# Metro_Mini_Rev_B.net
KiCad netlist of a schematic drawn in EAGLE
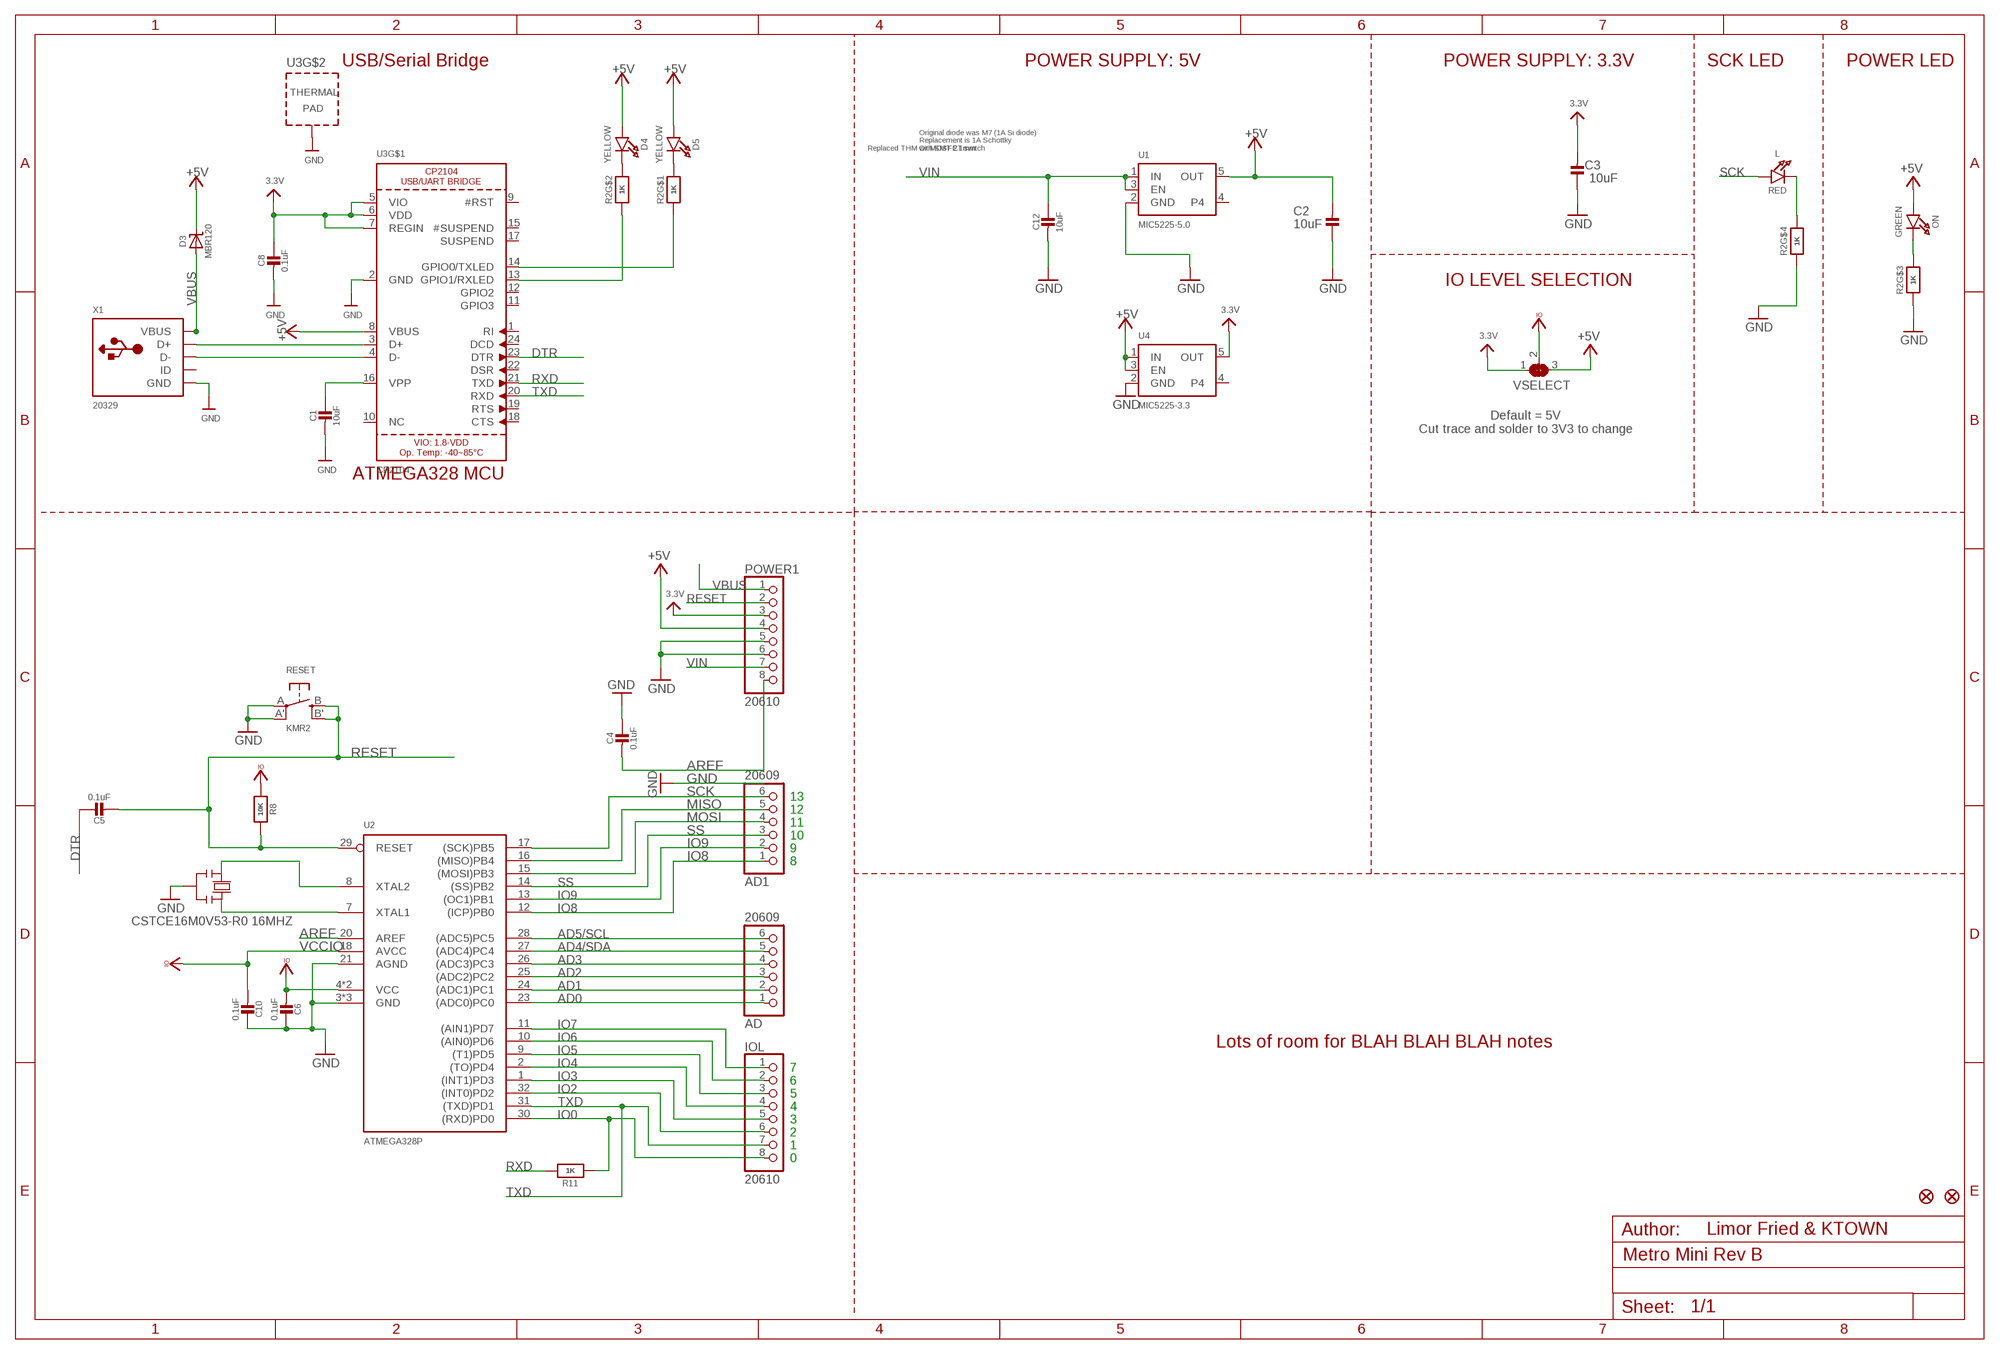
[diagram p0: schematic, sheet 1]

(export (version "E")
  (design (tool "Eeschema 10.0.6"))
  (components
    (comp (ref "AD")
      (value "20609")
      (footprint "eagle-import:1X06_ROUND")
      (libsource (lib "eagle-import") (part "HEADER-1X6ROUND"))
    )
    (comp (ref "AD1")
      (value "20609")
      (footprint "eagle-import:1X06_ROUND")
      (libsource (lib "eagle-import") (part "HEADER-1X6ROUND"))
    )
    (comp (ref "C1")
      (value "10uF")
      (footprint "eagle-import:0805-NO")
      (libsource (lib "eagle-import") (part "CAP_CERAMIC0805-NOOUTLINE"))
    )
    (comp (ref "C2")
      (value "10uF")
      (footprint "eagle-import:0805-NO")
      (libsource (lib "eagle-import") (part "CAP_CERAMIC0805-NOOUTLINE"))
    )
    (comp (ref "C3")
      (value "10uF")
      (footprint "eagle-import:0805-NO")
      (libsource (lib "eagle-import") (part "CAP_CERAMIC0805-NOOUTLINE"))
    )
    (comp (ref "C4")
      (value "0.1uF")
      (footprint "eagle-import:0805-NO")
      (libsource (lib "eagle-import") (part "CAP_CERAMIC0805-NOOUTLINE"))
    )
    (comp (ref "C5")
      (value "0.1uF")
      (footprint "eagle-import:_0805MP")
      (libsource (lib "eagle-import") (part "CAP_CERAMIC_0805MP"))
    )
    (comp (ref "C6")
      (value "0.1uF")
      (footprint "eagle-import:0805-NO")
      (libsource (lib "eagle-import") (part "CAP_CERAMIC0805-NOOUTLINE"))
    )
    (comp (ref "C8")
      (value "0.1uF")
      (footprint "eagle-import:0805-NO")
      (libsource (lib "eagle-import") (part "CAP_CERAMIC0805-NOOUTLINE"))
    )
    (comp (ref "C10")
      (value "0.1uF")
      (footprint "eagle-import:0805-NO")
      (libsource (lib "eagle-import") (part "CAP_CERAMIC0805-NOOUTLINE"))
    )
    (comp (ref "C12")
      (value "10uF")
      (footprint "eagle-import:0805-NO")
      (libsource (lib "eagle-import") (part "CAP_CERAMIC0805-NOOUTLINE"))
    )
    (comp (ref "D3")
      (value "MBR120")
      (footprint "eagle-import:SOD-123")
      (libsource (lib "eagle-import") (part "DIODE-SCHOTTKYSOD-123"))
    )
    (comp (ref "D4")
      (value "YELLOW")
      (footprint "eagle-import:CHIPLED_0805_NOOUTLINE")
      (libsource (lib "eagle-import") (part "LED0805_NOOUTLINE"))
    )
    (comp (ref "D5")
      (value "YELLOW")
      (footprint "eagle-import:CHIPLED_0805_NOOUTLINE")
      (libsource (lib "eagle-import") (part "LED0805_NOOUTLINE"))
    )
    (comp (ref "FD1")
      (value "FIDUCIAL\"\"")
      (footprint "eagle-import:FIDUCIAL_1MM")
      (libsource (lib "eagle-import") (part "FIDUCIAL{dblquote}{dblquote}"))
    )
    (comp (ref "FD2")
      (value "FIDUCIAL\"\"")
      (footprint "eagle-import:FIDUCIAL_1MM")
      (libsource (lib "eagle-import") (part "FIDUCIAL{dblquote}{dblquote}"))
    )
    (comp (ref "IOL")
      (value "20610")
      (footprint "eagle-import:1X08_ROUND")
      (libsource (lib "eagle-import") (part "HEADER-1X8ROUND"))
    )
    (comp (ref "L")
      (value "RED")
      (footprint "eagle-import:CHIPLED_0805_NOOUTLINE")
      (libsource (lib "eagle-import") (part "LED0805_NOOUTLINE"))
    )
    (comp (ref "ON")
      (value "GREEN")
      (footprint "eagle-import:CHIPLED_0805_NOOUTLINE")
      (libsource (lib "eagle-import") (part "LED0805_NOOUTLINE"))
    )
    (comp (ref "POWER1")
      (value "20610")
      (footprint "eagle-import:1X08_ROUND_70")
      (libsource (lib "eagle-import") (part "HEADER-1X870MIL"))
    )
    (comp (ref "R2")
      (value "1K")
      (footprint "eagle-import:RESPACK_4X0603")
      (libsource (lib "eagle-import") (part "RESISTOR_4PACK"))
    )
    (comp (ref "R8")
      (value "10K")
      (footprint "eagle-import:0805-NO")
      (libsource (lib "eagle-import") (part "RESISTOR0805_NOOUTLINE"))
    )
    (comp (ref "R11")
      (value "1K")
      (footprint "eagle-import:0805-NO")
      (libsource (lib "eagle-import") (part "RESISTOR0805_NOOUTLINE"))
    )
    (comp (ref "RESET")
      (value "KMR2")
      (footprint "eagle-import:BTN_KMR2_4.6X2.8")
      (libsource (lib "eagle-import") (part "SWITCH_TACT_SMT4.6X2.8"))
    )
    (comp (ref "U1")
      (value "MIC5225-5.0")
      (footprint "eagle-import:SOT23-5")
      (libsource (lib "eagle-import") (part "VREG_SOT23-5"))
    )
    (comp (ref "U2")
      (value "ATMEGA328P")
      (footprint "eagle-import:MLF32-TH")
      (libsource (lib "eagle-import") (part "ATMEGA328P"))
    )
    (comp (ref "U3")
      (value "CP2104")
      (footprint "eagle-import:QFN24_4MM_SMSC")
      (libsource (lib "eagle-import") (part "CP2104"))
    )
    (comp (ref "U4")
      (value "MIC5225-3.3")
      (footprint "eagle-import:SOT23-5")
      (libsource (lib "eagle-import") (part "VREG_SOT23-5"))
    )
    (comp (ref "VSELECT")
      (value "SOLDERJUMPER_2WAY")
      (footprint "eagle-import:SOLDERJUMPER_2WAY_OPEN_NOPASTE")
      (libsource (lib "eagle-import") (part "SOLDERJUMPER_2WAY"))
    )
    (comp (ref "X1")
      (value "20329")
      (footprint "eagle-import:4UCONN_20329_V2")
      (libsource (lib "eagle-import") (part "USB_MICRO_20329_V2"))
    )
    (comp (ref "Y2")
      (value "CSTCE16M0V53-R0 16MHZ")
      (footprint "eagle-import:RESONATOR")
      (libsource (lib "eagle-import") (part "RESONATORMU"))
    )
  )
  (nets
    (net (code "1") (name "+5V") (class "Default")
      (node (ref "C2") (pin "2") (pinfunction "2_2") (pintype "passive"))
      (node (ref "D3") (pin "C") (pinfunction "C_C") (pintype "passive"))
      (node (ref "D4") (pin "A") (pinfunction "A_A") (pintype "passive"))
      (node (ref "D5") (pin "A") (pinfunction "A_A") (pintype "passive"))
      (node (ref "ON") (pin "A") (pinfunction "A_A") (pintype "passive"))
      (node (ref "POWER1") (pin "4") (pinfunction "4_4") (pintype "passive"))
      (node (ref "U1") (pin "5") (pinfunction "OUT_5") (pintype "power_in"))
      (node (ref "U3") (pin "8") (pinfunction "VBUS_8") (pintype "power_in"))
      (node (ref "U4") (pin "1") (pinfunction "IN_1") (pintype "power_in"))
      (node (ref "U4") (pin "3") (pinfunction "EN_3") (pintype "input"))
      (node (ref "VSELECT") (pin "3") (pinfunction "3_3") (pintype "passive"))
    )
    (net (code "2") (name "/AD0") (class "Default")
      (node (ref "AD") (pin "1") (pinfunction "1_1") (pintype "passive"))
      (node (ref "U2") (pin "23") (pinfunction "(ADC0)PC0_23") (pintype "bidirectional"))
    )
    (net (code "3") (name "/AD1") (class "Default")
      (node (ref "AD") (pin "2") (pinfunction "2_2") (pintype "passive"))
      (node (ref "U2") (pin "24") (pinfunction "(ADC1)PC1_24") (pintype "bidirectional"))
    )
    (net (code "4") (name "/AD2") (class "Default")
      (node (ref "AD") (pin "3") (pinfunction "3_3") (pintype "passive"))
      (node (ref "U2") (pin "25") (pinfunction "(ADC2)PC2_25") (pintype "bidirectional"))
    )
    (net (code "5") (name "/AD3") (class "Default")
      (node (ref "AD") (pin "4") (pinfunction "4_4") (pintype "passive"))
      (node (ref "U2") (pin "26") (pinfunction "(ADC3)PC3_26") (pintype "bidirectional"))
    )
    (net (code "6") (name "/AD4{slash}SDA") (class "Default")
      (node (ref "AD") (pin "5") (pinfunction "5_5") (pintype "passive"))
      (node (ref "U2") (pin "27") (pinfunction "(ADC4)PC4_27") (pintype "bidirectional"))
    )
    (net (code "7") (name "/AD5{slash}SCL") (class "Default")
      (node (ref "AD") (pin "6") (pinfunction "6_6") (pintype "passive"))
      (node (ref "U2") (pin "28") (pinfunction "(ADC5)PC5_28") (pintype "bidirectional"))
    )
    (net (code "8") (name "/AREF") (class "Default")
      (node (ref "C4") (pin "2") (pinfunction "2_2") (pintype "passive"))
      (node (ref "POWER1") (pin "8") (pinfunction "8_8") (pintype "passive"))
      (node (ref "U2") (pin "20") (pinfunction "AREF_20") (pintype "power_in"))
    )
    (net (code "9") (name "/DTR") (class "Default")
      (node (ref "C5") (pin "1") (pinfunction "1_1") (pintype "passive"))
      (node (ref "U3") (pin "23") (pinfunction "DTR_23") (pintype "output"))
    )
    (net (code "10") (name "/IO0") (class "Default")
      (node (ref "IOL") (pin "8") (pinfunction "8_8") (pintype "passive"))
      (node (ref "R11") (pin "1") (pinfunction "1_1") (pintype "passive"))
      (node (ref "U2") (pin "30") (pinfunction "(RXD)PD0_30") (pintype "bidirectional"))
    )
    (net (code "11") (name "/IO2") (class "Default")
      (node (ref "IOL") (pin "6") (pinfunction "6_6") (pintype "passive"))
      (node (ref "U2") (pin "32") (pinfunction "(INT0)PD2_32") (pintype "bidirectional"))
    )
    (net (code "12") (name "/IO3") (class "Default")
      (node (ref "IOL") (pin "5") (pinfunction "5_5") (pintype "passive"))
      (node (ref "U2") (pin "1") (pinfunction "(INT1)PD3_1") (pintype "bidirectional"))
    )
    (net (code "13") (name "/IO4") (class "Default")
      (node (ref "IOL") (pin "4") (pinfunction "4_4") (pintype "passive"))
      (node (ref "U2") (pin "2") (pinfunction "(TO)PD4_2") (pintype "bidirectional"))
    )
    (net (code "14") (name "/IO5") (class "Default")
      (node (ref "IOL") (pin "3") (pinfunction "3_3") (pintype "passive"))
      (node (ref "U2") (pin "9") (pinfunction "(T1)PD5_9") (pintype "bidirectional"))
    )
    (net (code "15") (name "/IO6") (class "Default")
      (node (ref "IOL") (pin "2") (pinfunction "2_2") (pintype "passive"))
      (node (ref "U2") (pin "10") (pinfunction "(AIN0)PD6_10") (pintype "bidirectional"))
    )
    (net (code "16") (name "/IO7") (class "Default")
      (node (ref "IOL") (pin "1") (pinfunction "1_1") (pintype "passive"))
      (node (ref "U2") (pin "11") (pinfunction "(AIN1)PD7_11") (pintype "bidirectional"))
    )
    (net (code "17") (name "/IO8") (class "Default")
      (node (ref "AD1") (pin "1") (pinfunction "1_1") (pintype "passive"))
      (node (ref "U2") (pin "12") (pinfunction "(ICP)PB0_12") (pintype "bidirectional"))
    )
    (net (code "18") (name "/IO9") (class "Default")
      (node (ref "AD1") (pin "2") (pinfunction "2_2") (pintype "passive"))
      (node (ref "U2") (pin "13") (pinfunction "(OC1)PB1_13") (pintype "bidirectional"))
    )
    (net (code "19") (name "/MISO") (class "Default")
      (node (ref "AD1") (pin "5") (pinfunction "5_5") (pintype "passive"))
      (node (ref "U2") (pin "16") (pinfunction "(MISO)PB4_16") (pintype "bidirectional"))
    )
    (net (code "20") (name "/MOSI") (class "Default")
      (node (ref "AD1") (pin "4") (pinfunction "4_4") (pintype "passive"))
      (node (ref "U2") (pin "15") (pinfunction "(MOSI)PB3_15") (pintype "bidirectional"))
    )
    (net (code "21") (name "/RESET") (class "Default")
      (node (ref "C5") (pin "2") (pinfunction "2_2") (pintype "passive"))
      (node (ref "POWER1") (pin "2") (pinfunction "2_2") (pintype "passive"))
      (node (ref "R8") (pin "1") (pinfunction "1_1") (pintype "passive"))
      (node (ref "RESET") (pin "B") (pinfunction "S_B") (pintype "passive"))
      (node (ref "RESET") (pin "B'") (pinfunction "S1_B'") (pintype "passive"))
      (node (ref "U2") (pin "29") (pinfunction "RESET_29") (pintype "bidirectional"))
    )
    (net (code "22") (name "/RXD") (class "Default")
      (node (ref "R11") (pin "2") (pinfunction "2_2") (pintype "passive"))
      (node (ref "U3") (pin "21") (pinfunction "TXD_21") (pintype "output"))
    )
    (net (code "23") (name "/SCK") (class "Default")
      (node (ref "AD1") (pin "6") (pinfunction "6_6") (pintype "passive"))
      (node (ref "L") (pin "A") (pinfunction "A_A") (pintype "passive"))
      (node (ref "U2") (pin "17") (pinfunction "(SCK)PB5_17") (pintype "bidirectional"))
    )
    (net (code "24") (name "/SS") (class "Default")
      (node (ref "AD1") (pin "3") (pinfunction "3_3") (pintype "passive"))
      (node (ref "U2") (pin "14") (pinfunction "(SS)PB2_14") (pintype "bidirectional"))
    )
    (net (code "25") (name "/TXD") (class "Default")
      (node (ref "IOL") (pin "7") (pinfunction "7_7") (pintype "passive"))
      (node (ref "U2") (pin "31") (pinfunction "(TXD)PD1_31") (pintype "bidirectional"))
      (node (ref "U3") (pin "20") (pinfunction "RXD_20") (pintype "input"))
    )
    (net (code "26") (name "/VBUS") (class "Default")
      (node (ref "D3") (pin "A") (pinfunction "A_A") (pintype "passive"))
      (node (ref "POWER1") (pin "1") (pinfunction "1_1") (pintype "passive"))
      (node (ref "X1") (pin "VBUS") (pinfunction "VBUS_VBUS") (pintype "power_in"))
    )
    (net (code "27") (name "/VIN") (class "Default")
      (node (ref "C12") (pin "1") (pinfunction "1_1") (pintype "passive"))
      (node (ref "POWER1") (pin "7") (pinfunction "7_7") (pintype "passive"))
      (node (ref "U1") (pin "1") (pinfunction "IN_1") (pintype "power_in"))
      (node (ref "U1") (pin "3") (pinfunction "EN_3") (pintype "input"))
    )
    (net (code "28") (name "3.3V") (class "Default")
      (node (ref "C3") (pin "2") (pinfunction "2_2") (pintype "passive"))
      (node (ref "C8") (pin "1") (pinfunction "1_1") (pintype "passive"))
      (node (ref "POWER1") (pin "3") (pinfunction "3_3") (pintype "passive"))
      (node (ref "U3") (pin "5") (pinfunction "VIO_5") (pintype "power_in"))
      (node (ref "U3") (pin "6") (pinfunction "VDD_6") (pintype "power_in"))
      (node (ref "U3") (pin "7") (pinfunction "REGIN_7") (pintype "power_in"))
      (node (ref "U4") (pin "5") (pinfunction "OUT_5") (pintype "power_in"))
      (node (ref "VSELECT") (pin "1") (pinfunction "1_1") (pintype "passive"))
    )
    (net (code "29") (name "GND") (class "Default")
      (node (ref "C1") (pin "2") (pinfunction "2_2") (pintype "passive"))
      (node (ref "C10") (pin "1") (pinfunction "1_1") (pintype "passive"))
      (node (ref "C12") (pin "2") (pinfunction "2_2") (pintype "passive"))
      (node (ref "C2") (pin "1") (pinfunction "1_1") (pintype "passive"))
      (node (ref "C3") (pin "1") (pinfunction "1_1") (pintype "passive"))
      (node (ref "C4") (pin "1") (pinfunction "1_1") (pintype "passive"))
      (node (ref "C6") (pin "1") (pinfunction "1_1") (pintype "passive"))
      (node (ref "C8") (pin "2") (pinfunction "2_2") (pintype "passive"))
      (node (ref "POWER1") (pin "5") (pinfunction "5_5") (pintype "passive"))
      (node (ref "POWER1") (pin "6") (pinfunction "6_6") (pintype "passive"))
      (node (ref "R2") (pin "3") (pinfunction "1_3") (pintype "passive"))
      (node (ref "R2") (pin "4") (pinfunction "1_4") (pintype "passive"))
      (node (ref "RESET") (pin "A") (pinfunction "P_A") (pintype "passive"))
      (node (ref "RESET") (pin "A'") (pinfunction "P1_A'") (pintype "passive"))
      (node (ref "U1") (pin "2") (pinfunction "GND_2") (pintype "power_in"))
      (node (ref "U2") (pin "21") (pinfunction "AGND_21") (pintype "power_in"))
      (node (ref "U2") (pin "3") (pinfunction "GND_3") (pintype "power_in"))
      (node (ref "U2") (pin "5") (pinfunction "GND_5") (pintype "power_in"))
      (node (ref "U2") (pin "TH") (pinfunction "GND_TH") (pintype "power_in"))
      (node (ref "U3") (pin "2") (pinfunction "GND_2") (pintype "power_in"))
      (node (ref "U3") (pin "THERM") (pinfunction "TP_THERM") (pintype "power_in"))
      (node (ref "U4") (pin "2") (pinfunction "GND_2") (pintype "power_in"))
      (node (ref "X1") (pin "BASE@1") (pinfunction "GND_BASE@1") (pintype "power_in"))
      (node (ref "X1") (pin "BASE@2") (pinfunction "GND_BASE@2") (pintype "power_in"))
      (node (ref "X1") (pin "GND") (pinfunction "GND_GND") (pintype "power_in"))
      (node (ref "X1") (pin "SPRT@1") (pinfunction "GND_SPRT@1") (pintype "power_in"))
      (node (ref "X1") (pin "SPRT@2") (pinfunction "GND_SPRT@2") (pintype "power_in"))
      (node (ref "X1") (pin "SPRT@3") (pinfunction "GND_SPRT@3") (pintype "power_in"))
      (node (ref "X1") (pin "SPRT@4") (pinfunction "GND_SPRT@4") (pintype "power_in"))
      (node (ref "Y2") (pin "2") (pinfunction "2_2") (pintype "passive"))
    )
    (net (code "30") (name "Net-(R2A-2)") (class "Default")
      (node (ref "D5") (pin "C") (pinfunction "C_C") (pintype "passive"))
      (node (ref "R2") (pin "8") (pinfunction "2_8") (pintype "passive"))
    )
    (net (code "31") (name "Net-(R2B-1)") (class "Default")
      (node (ref "R2") (pin "2") (pinfunction "1_2") (pintype "passive"))
      (node (ref "U3") (pin "13") (pinfunction "GPIO1/RXLED_13") (pintype "bidirectional"))
    )
    (net (code "32") (name "Net-(R2B-2)") (class "Default")
      (node (ref "D4") (pin "C") (pinfunction "C_C") (pintype "passive"))
      (node (ref "R2") (pin "7") (pinfunction "2_7") (pintype "passive"))
    )
    (net (code "33") (name "Net-(R2C-2)") (class "Default")
      (node (ref "ON") (pin "C") (pinfunction "C_C") (pintype "passive"))
      (node (ref "R2") (pin "6") (pinfunction "2_6") (pintype "passive"))
    )
    (net (code "34") (name "Net-(R2D-2)") (class "Default")
      (node (ref "L") (pin "C") (pinfunction "C_C") (pintype "passive"))
      (node (ref "R2") (pin "5") (pinfunction "2_5") (pintype "passive"))
    )
    (net (code "35") (name "Net-(U2-XTAL1)") (class "Default")
      (node (ref "U2") (pin "7") (pinfunction "XTAL1_7") (pintype "bidirectional"))
      (node (ref "Y2") (pin "3") (pinfunction "3_3") (pintype "passive"))
    )
    (net (code "36") (name "Net-(U2-XTAL2)") (class "Default")
      (node (ref "U2") (pin "8") (pinfunction "XTAL2_8") (pintype "bidirectional"))
      (node (ref "Y2") (pin "1") (pinfunction "1_1") (pintype "passive"))
    )
    (net (code "37") (name "Net-(U3A-D+)") (class "Default")
      (node (ref "U3") (pin "3") (pinfunction "D+_3") (pintype "bidirectional"))
      (node (ref "X1") (pin "D+") (pinfunction "D+_D+") (pintype "bidirectional"))
    )
    (net (code "38") (name "Net-(U3A-D-)") (class "Default")
      (node (ref "U3") (pin "4") (pinfunction "D-_4") (pintype "bidirectional"))
      (node (ref "X1") (pin "D-") (pinfunction "D-_D-") (pintype "bidirectional"))
    )
    (net (code "39") (name "Net-(U3A-GPIO0{slash}TXLED)") (class "Default")
      (node (ref "R2") (pin "1") (pinfunction "1_1") (pintype "passive"))
      (node (ref "U3") (pin "14") (pinfunction "GPIO0/TXLED_14") (pintype "bidirectional"))
    )
    (net (code "40") (name "Net-(U3A-VPP)") (class "Default")
      (node (ref "C1") (pin "1") (pinfunction "1_1") (pintype "passive"))
      (node (ref "U3") (pin "16") (pinfunction "VPP_16") (pintype "bidirectional"))
    )
    (net (code "41") (name "VCCIO") (class "Default")
      (node (ref "C10") (pin "2") (pinfunction "2_2") (pintype "passive"))
      (node (ref "C6") (pin "2") (pinfunction "2_2") (pintype "passive"))
      (node (ref "R8") (pin "2") (pinfunction "2_2") (pintype "passive"))
      (node (ref "U2") (pin "18") (pinfunction "AVCC_18") (pintype "power_in"))
      (node (ref "U2") (pin "4") (pinfunction "VCC_4") (pintype "power_in"))
      (node (ref "U2") (pin "6") (pinfunction "VCC_6") (pintype "power_in"))
      (node (ref "VSELECT") (pin "2") (pinfunction "2_2") (pintype "passive"))
    )
    (net (code "42") (name "unconnected-(U1-P4-Pad4)") (class "Default")
      (node (ref "U1") (pin "4") (pinfunction "P4_4") (pintype "bidirectional"))
    )
    (net (code "43") (name "unconnected-(U3A-#RST-Pad9)") (class "Default")
      (node (ref "U3") (pin "9") (pinfunction "#RST_9") (pintype "bidirectional"))
    )
    (net (code "44") (name "unconnected-(U3A-#SUSPEND-Pad15)") (class "Default")
      (node (ref "U3") (pin "15") (pinfunction "#SUSPEND_15") (pintype "output"))
    )
    (net (code "45") (name "unconnected-(U3A-CTS-Pad18)") (class "Default")
      (node (ref "U3") (pin "18") (pinfunction "CTS_18") (pintype "input"))
    )
    (net (code "46") (name "unconnected-(U3A-DCD-Pad24)") (class "Default")
      (node (ref "U3") (pin "24") (pinfunction "DCD_24") (pintype "input"))
    )
    (net (code "47") (name "unconnected-(U3A-DSR-Pad22)") (class "Default")
      (node (ref "U3") (pin "22") (pinfunction "DSR_22") (pintype "input"))
    )
    (net (code "48") (name "unconnected-(U3A-GPIO2-Pad12)") (class "Default")
      (node (ref "U3") (pin "12") (pinfunction "GPIO2_12") (pintype "bidirectional"))
    )
    (net (code "49") (name "unconnected-(U3A-GPIO3-Pad11)") (class "Default")
      (node (ref "U3") (pin "11") (pinfunction "GPIO3_11") (pintype "bidirectional"))
    )
    (net (code "50") (name "unconnected-(U3A-NC-Pad10)") (class "Default")
      (node (ref "U3") (pin "10") (pinfunction "NC_10") (pintype "no_connect"))
    )
    (net (code "51") (name "unconnected-(U3A-RI-Pad1)") (class "Default")
      (node (ref "U3") (pin "1") (pinfunction "RI_1") (pintype "input"))
    )
    (net (code "52") (name "unconnected-(U3A-RTS-Pad19)") (class "Default")
      (node (ref "U3") (pin "19") (pinfunction "RTS_19") (pintype "output"))
    )
    (net (code "53") (name "unconnected-(U3A-SUSPEND-Pad17)") (class "Default")
      (node (ref "U3") (pin "17") (pinfunction "SUSPEND_17") (pintype "output"))
    )
    (net (code "54") (name "unconnected-(U4-P4-Pad4)") (class "Default")
      (node (ref "U4") (pin "4") (pinfunction "P4_4") (pintype "bidirectional"))
    )
    (net (code "55") (name "unconnected-(X1-PadID)") (class "Default")
      (node (ref "X1") (pin "ID") (pinfunction "ID_ID") (pintype "bidirectional"))
    )
  )
)
